# Sheet1.net
KiCad netlist of a schematic drawn in Altium Designer
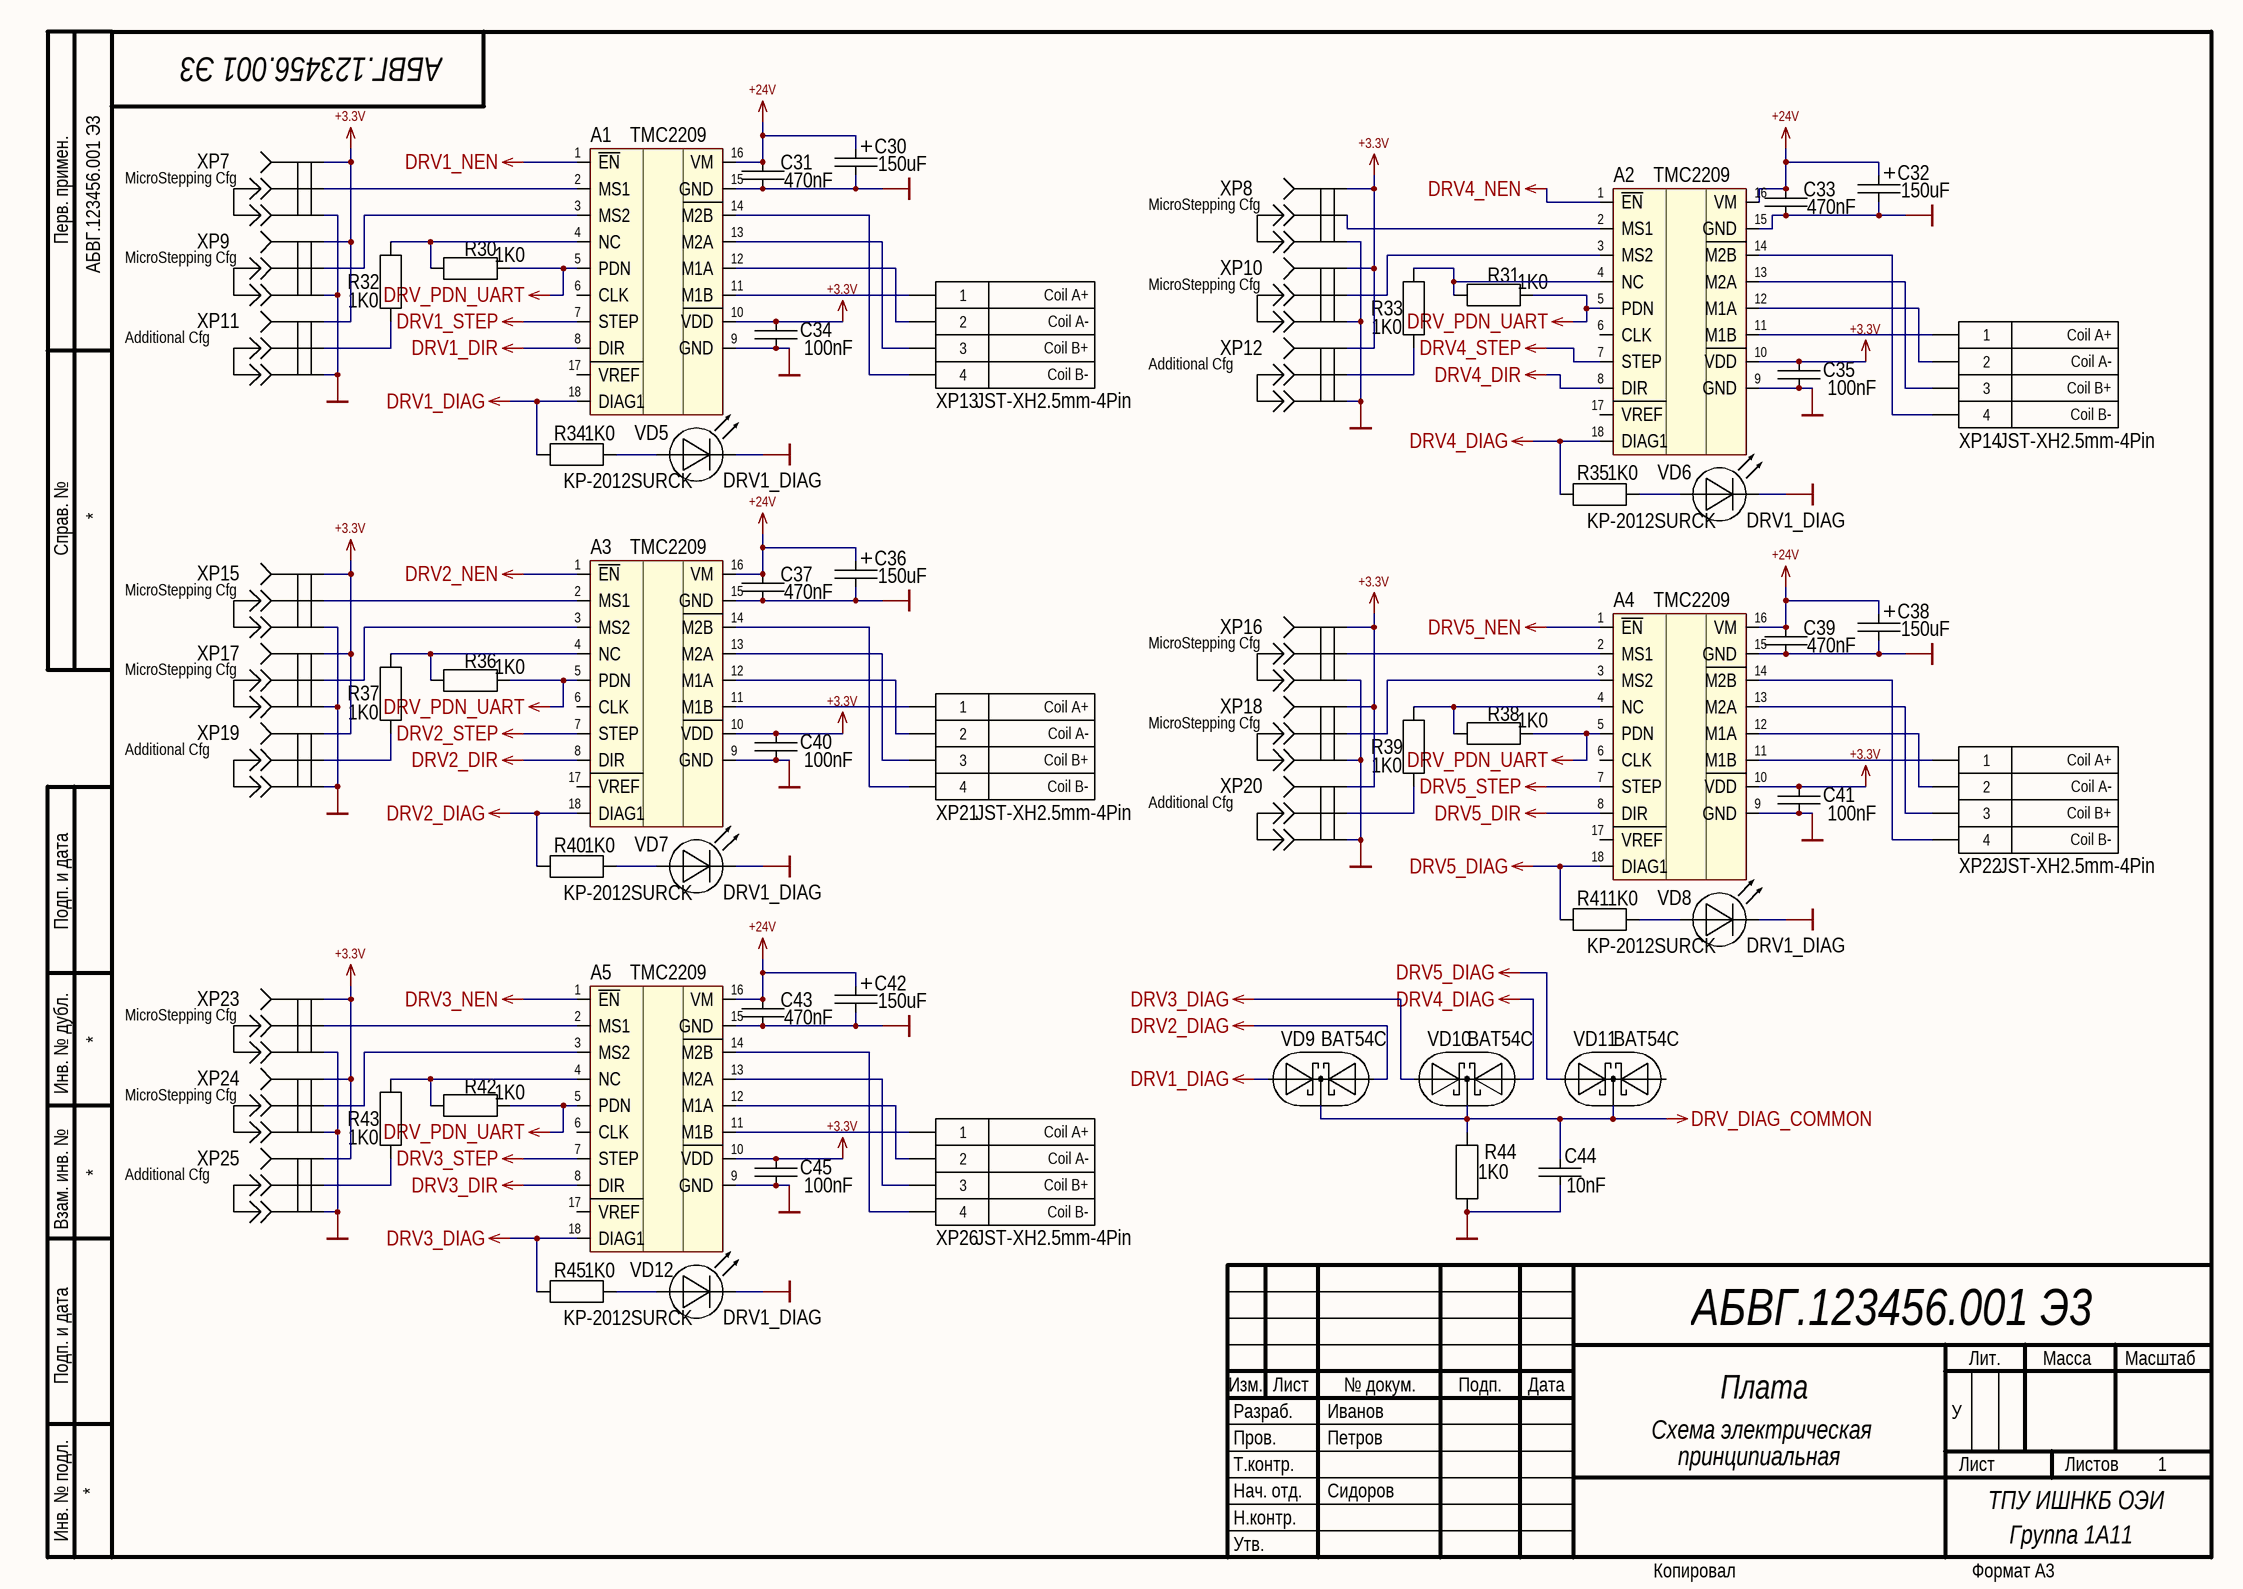
[diagram p0: Sheet1.SchDoc]

(export (version "E")
  (design (tool "Eeschema 10.0.6"))
  (components
    (comp (ref "A1")
      (value "TMC2209")
      (footprint "TMC2209_module")
      (libsource (lib "Digital IC Library") (part "TMC2209_module"))
    )
    (comp (ref "A2")
      (value "TMC2209")
      (footprint "TMC2209_module")
      (libsource (lib "Digital IC Library") (part "TMC2209_module"))
    )
    (comp (ref "A3")
      (value "TMC2209")
      (footprint "TMC2209_module")
      (libsource (lib "Digital IC Library") (part "TMC2209_module"))
    )
    (comp (ref "A4")
      (value "TMC2209")
      (footprint "TMC2209_module")
      (libsource (lib "Digital IC Library") (part "TMC2209_module"))
    )
    (comp (ref "A5")
      (value "TMC2209")
      (footprint "TMC2209_module")
      (libsource (lib "Digital IC Library") (part "TMC2209_module"))
    )
    (comp (ref "C30")
      (value "150uF")
      (footprint "CapAl8X11.5X3.5RA")
      (description "LOW IMPEDANCE ALUMINUM ELECTROLYTIC CAPACITORS CapAl8X11.5X3.5 150uF±20% 35 V 105⁰С")
      (fields (field (name "TOLERANCE") "±20%") (field (name "VOLTAGE") "35 V"))
      (libsource (lib "Passive DataBase") (part "CapacitorPol"))
    )
    (comp (ref "C31")
      (value "470nF")
      (footprint "CAP0805")
      (description "GENERAL PURPOSE CLASS 2 CERAMIC CAPACITORS CAP0805 470nF±10% 50 V X7R")
      (fields (field (name "TOLERANCE") "±10%") (field (name "VOLTAGE") "50 V"))
      (libsource (lib "Passive DataBase") (part "Capacitor"))
    )
    (comp (ref "C32")
      (value "150uF")
      (footprint "CapAl8X11.5X3.5")
      (description "LOW IMPEDANCE ALUMINUM ELECTROLYTIC CAPACITORS CapAl8X11.5X3.5 150uF±20% 35 V 105⁰С")
      (fields (field (name "TOLERANCE") "±20%") (field (name "VOLTAGE") "35 V"))
      (libsource (lib "Passive DataBase") (part "CapacitorPol"))
    )
    (comp (ref "C33")
      (value "470nF")
      (footprint "CAP0805")
      (description "GENERAL PURPOSE CLASS 2 CERAMIC CAPACITORS CAP0805 470nF±10% 50 V X7R")
      (fields (field (name "TOLERANCE") "±10%") (field (name "VOLTAGE") "50 V"))
      (libsource (lib "Passive DataBase") (part "Capacitor"))
    )
    (comp (ref "C34")
      (value "100nF")
      (footprint "CAP0805")
      (description "GENERAL PURPOSE CLASS 2 CERAMIC CAPACITORS CAP0805 100nF±10% 50 V X7R")
      (fields (field (name "TOLERANCE") "±10%") (field (name "VOLTAGE") "50 V"))
      (libsource (lib "Passive DataBase") (part "Capacitor"))
    )
    (comp (ref "C35")
      (value "100nF")
      (footprint "CAP0805")
      (description "GENERAL PURPOSE CLASS 2 CERAMIC CAPACITORS CAP0805 100nF±10% 50 V X7R")
      (fields (field (name "TOLERANCE") "±10%") (field (name "VOLTAGE") "50 V"))
      (libsource (lib "Passive DataBase") (part "Capacitor"))
    )
    (comp (ref "C36")
      (value "150uF")
      (footprint "CapAl8X11.5X3.5RA")
      (description "LOW IMPEDANCE ALUMINUM ELECTROLYTIC CAPACITORS CapAl8X11.5X3.5 150uF±20% 35 V 105⁰С")
      (fields (field (name "TOLERANCE") "±20%") (field (name "VOLTAGE") "35 V"))
      (libsource (lib "Passive DataBase") (part "CapacitorPol"))
    )
    (comp (ref "C37")
      (value "470nF")
      (footprint "CAP0805")
      (description "GENERAL PURPOSE CLASS 2 CERAMIC CAPACITORS CAP0805 470nF±10% 50 V X7R")
      (fields (field (name "TOLERANCE") "±10%") (field (name "VOLTAGE") "50 V"))
      (libsource (lib "Passive DataBase") (part "Capacitor"))
    )
    (comp (ref "C38")
      (value "150uF")
      (footprint "CapAl8X11.5X3.5RA")
      (description "LOW IMPEDANCE ALUMINUM ELECTROLYTIC CAPACITORS CapAl8X11.5X3.5 150uF±20% 35 V 105⁰С")
      (fields (field (name "TOLERANCE") "±20%") (field (name "VOLTAGE") "35 V"))
      (libsource (lib "Passive DataBase") (part "CapacitorPol"))
    )
    (comp (ref "C39")
      (value "470nF")
      (footprint "CAP0805")
      (description "GENERAL PURPOSE CLASS 2 CERAMIC CAPACITORS CAP0805 470nF±10% 50 V X7R")
      (fields (field (name "TOLERANCE") "±10%") (field (name "VOLTAGE") "50 V"))
      (libsource (lib "Passive DataBase") (part "Capacitor"))
    )
    (comp (ref "C40")
      (value "100nF")
      (footprint "CAP0805")
      (description "GENERAL PURPOSE CLASS 2 CERAMIC CAPACITORS CAP0805 100nF±10% 50 V X7R")
      (fields (field (name "TOLERANCE") "±10%") (field (name "VOLTAGE") "50 V"))
      (libsource (lib "Passive DataBase") (part "Capacitor"))
    )
    (comp (ref "C41")
      (value "100nF")
      (footprint "CAP0805")
      (description "GENERAL PURPOSE CLASS 2 CERAMIC CAPACITORS CAP0805 100nF±10% 50 V X7R")
      (fields (field (name "TOLERANCE") "±10%") (field (name "VOLTAGE") "50 V"))
      (libsource (lib "Passive DataBase") (part "Capacitor"))
    )
    (comp (ref "C42")
      (value "150uF")
      (footprint "CapAl8X11.5X3.5RA")
      (description "LOW IMPEDANCE ALUMINUM ELECTROLYTIC CAPACITORS CapAl8X11.5X3.5 150uF±20% 35 V 105⁰С")
      (fields (field (name "TOLERANCE") "±20%") (field (name "VOLTAGE") "35 V"))
      (libsource (lib "Passive DataBase") (part "CapacitorPol"))
    )
    (comp (ref "C43")
      (value "470nF")
      (footprint "CAP0805")
      (description "GENERAL PURPOSE CLASS 2 CERAMIC CAPACITORS CAP0805 470nF±10% 50 V X7R")
      (fields (field (name "TOLERANCE") "±10%") (field (name "VOLTAGE") "50 V"))
      (libsource (lib "Passive DataBase") (part "Capacitor"))
    )
    (comp (ref "C44")
      (value "10nF")
      (footprint "CAP0805")
      (description "GENERAL PURPOSE CLASS 1 CERAMIC CAPACITORS CAP0805 10nF±5% 50 V NP0")
      (fields (field (name "TOLERANCE") "±5%") (field (name "VOLTAGE") "50 V"))
      (libsource (lib "Passive DataBase") (part "Capacitor"))
    )
    (comp (ref "C45")
      (value "100nF")
      (footprint "CAP0805")
      (description "GENERAL PURPOSE CLASS 2 CERAMIC CAPACITORS CAP0805 100nF±10% 50 V X7R")
      (fields (field (name "TOLERANCE") "±10%") (field (name "VOLTAGE") "50 V"))
      (libsource (lib "Passive DataBase") (part "Capacitor"))
    )
    (comp (ref "R30")
      (value "1K0")
      (footprint "RES0805")
      (description "GENERAL PURPOSE CHIP RESISTORS RES0805 1K0±5% 150V 0.125W")
      (fields (field (name "TOLERANCE") "±5%") (field (name "VOLTAGE") "150V"))
      (libsource (lib "Passive DataBase") (part "Resistor"))
    )
    (comp (ref "R31")
      (value "1K0")
      (footprint "RES0805")
      (description "GENERAL PURPOSE CHIP RESISTORS RES0805 1K0±5% 150V 0.125W")
      (fields (field (name "TOLERANCE") "±5%") (field (name "VOLTAGE") "150V"))
      (libsource (lib "Passive DataBase") (part "Resistor"))
    )
    (comp (ref "R32")
      (value "1K0")
      (footprint "RES0805")
      (description "GENERAL PURPOSE CHIP RESISTORS RES0805 1K0±5% 150V 0.125W")
      (fields (field (name "TOLERANCE") "±5%") (field (name "VOLTAGE") "150V"))
      (libsource (lib "Passive DataBase") (part "Resistor"))
    )
    (comp (ref "R33")
      (value "1K0")
      (footprint "RES0805")
      (description "GENERAL PURPOSE CHIP RESISTORS RES0805 1K0±5% 150V 0.125W")
      (fields (field (name "TOLERANCE") "±5%") (field (name "VOLTAGE") "150V"))
      (libsource (lib "Passive DataBase") (part "Resistor"))
    )
    (comp (ref "R34")
      (value "1K0")
      (footprint "RES0805")
      (description "GENERAL PURPOSE CHIP RESISTORS RES0805 1K0±5% 150V 0.125W")
      (fields (field (name "TOLERANCE") "±5%") (field (name "VOLTAGE") "150V"))
      (libsource (lib "Passive DataBase") (part "Resistor"))
    )
    (comp (ref "R35")
      (value "1K0")
      (footprint "RES0805")
      (description "GENERAL PURPOSE CHIP RESISTORS RES0805 1K0±5% 150V 0.125W")
      (fields (field (name "TOLERANCE") "±5%") (field (name "VOLTAGE") "150V"))
      (libsource (lib "Passive DataBase") (part "Resistor"))
    )
    (comp (ref "R36")
      (value "1K0")
      (footprint "RES0805")
      (description "GENERAL PURPOSE CHIP RESISTORS RES0805 1K0±5% 150V 0.125W")
      (fields (field (name "TOLERANCE") "±5%") (field (name "VOLTAGE") "150V"))
      (libsource (lib "Passive DataBase") (part "Resistor"))
    )
    (comp (ref "R37")
      (value "1K0")
      (footprint "RES0805")
      (description "GENERAL PURPOSE CHIP RESISTORS RES0805 1K0±5% 150V 0.125W")
      (fields (field (name "TOLERANCE") "±5%") (field (name "VOLTAGE") "150V"))
      (libsource (lib "Passive DataBase") (part "Resistor"))
    )
    (comp (ref "R38")
      (value "1K0")
      (footprint "RES0805")
      (description "GENERAL PURPOSE CHIP RESISTORS RES0805 1K0±5% 150V 0.125W")
      (fields (field (name "TOLERANCE") "±5%") (field (name "VOLTAGE") "150V"))
      (libsource (lib "Passive DataBase") (part "Resistor"))
    )
    (comp (ref "R39")
      (value "1K0")
      (footprint "RES0805")
      (description "GENERAL PURPOSE CHIP RESISTORS RES0805 1K0±5% 150V 0.125W")
      (fields (field (name "TOLERANCE") "±5%") (field (name "VOLTAGE") "150V"))
      (libsource (lib "Passive DataBase") (part "Resistor"))
    )
    (comp (ref "R40")
      (value "1K0")
      (footprint "RES0805")
      (description "GENERAL PURPOSE CHIP RESISTORS RES0805 1K0±5% 150V 0.125W")
      (fields (field (name "TOLERANCE") "±5%") (field (name "VOLTAGE") "150V"))
      (libsource (lib "Passive DataBase") (part "Resistor"))
    )
    (comp (ref "R41")
      (value "1K0")
      (footprint "RES0805")
      (description "GENERAL PURPOSE CHIP RESISTORS RES0805 1K0±5% 150V 0.125W")
      (fields (field (name "TOLERANCE") "±5%") (field (name "VOLTAGE") "150V"))
      (libsource (lib "Passive DataBase") (part "Resistor"))
    )
    (comp (ref "R42")
      (value "1K0")
      (footprint "RES0805")
      (description "GENERAL PURPOSE CHIP RESISTORS RES0805 1K0±5% 150V 0.125W")
      (fields (field (name "TOLERANCE") "±5%") (field (name "VOLTAGE") "150V"))
      (libsource (lib "Passive DataBase") (part "Resistor"))
    )
    (comp (ref "R43")
      (value "1K0")
      (footprint "RES0805")
      (description "GENERAL PURPOSE CHIP RESISTORS RES0805 1K0±5% 150V 0.125W")
      (fields (field (name "TOLERANCE") "±5%") (field (name "VOLTAGE") "150V"))
      (libsource (lib "Passive DataBase") (part "Resistor"))
    )
    (comp (ref "R44")
      (value "1K0")
      (footprint "RES0805")
      (description "GENERAL PURPOSE CHIP RESISTORS RES0805 1K0±5% 150V 0.125W")
      (fields (field (name "TOLERANCE") "±5%") (field (name "VOLTAGE") "150V"))
      (libsource (lib "Passive DataBase") (part "Resistor"))
    )
    (comp (ref "R45")
      (value "1K0")
      (footprint "RES0805")
      (description "GENERAL PURPOSE CHIP RESISTORS RES0805 1K0±5% 150V 0.125W")
      (fields (field (name "TOLERANCE") "±5%") (field (name "VOLTAGE") "150V"))
      (libsource (lib "Passive DataBase") (part "Resistor"))
    )
    (comp (ref "VD5")
      (value "KP-2012SURCK (2.0V, 25mA, LED0805 RED)")
      (footprint "LED0805 RED")
      (description "LED SMD KP-2012SURCK (2.0V, 25mA, LED0805 RED)")
      (fields
        (field (name "MODEL") "KP-2012SURCK")
        (field (name "VOLTAGE") "2.0V")
        (field (name "PARTNUMBER") "KP-2012SURCK")
      )
      (libsource (lib "Discrete Semiconductors DataBase") (part "LED Single"))
    )
    (comp (ref "VD6")
      (value "KP-2012SURCK (2.0V, 25mA, LED0805 RED)")
      (footprint "LED0805 RED")
      (description "LED SMD KP-2012SURCK (2.0V, 25mA, LED0805 RED)")
      (fields
        (field (name "MODEL") "KP-2012SURCK")
        (field (name "VOLTAGE") "2.0V")
        (field (name "PARTNUMBER") "KP-2012SURCK")
      )
      (libsource (lib "Discrete Semiconductors DataBase") (part "LED Single"))
    )
    (comp (ref "VD7")
      (value "KP-2012SURCK (2.0V, 25mA, LED0805 RED)")
      (footprint "LED0805 RED")
      (description "LED SMD KP-2012SURCK (2.0V, 25mA, LED0805 RED)")
      (fields
        (field (name "MODEL") "KP-2012SURCK")
        (field (name "VOLTAGE") "2.0V")
        (field (name "PARTNUMBER") "KP-2012SURCK")
      )
      (libsource (lib "Discrete Semiconductors DataBase") (part "LED Single"))
    )
    (comp (ref "VD8")
      (value "KP-2012SURCK (2.0V, 25mA, LED0805 RED)")
      (footprint "LED0805 RED")
      (description "LED SMD KP-2012SURCK (2.0V, 25mA, LED0805 RED)")
      (fields
        (field (name "MODEL") "KP-2012SURCK")
        (field (name "VOLTAGE") "2.0V")
        (field (name "PARTNUMBER") "KP-2012SURCK")
      )
      (libsource (lib "Discrete Semiconductors DataBase") (part "LED Single"))
    )
    (comp (ref "VD9")
      (value "BAT54C (30 V, 200 mA, SOT23-3 DIODE (A1A2C))")
      (footprint "SOT23-3 DIODE (A1A2C)")
      (description "DIODE BAT54C (30 V, 200 mA, SOT23-3 DIODE (A1A2C), NXP)")
      (fields
        (field (name "MODEL") "BAT54C")
        (field (name "VOLTAGE") "30 V")
        (field (name "PARTNUMBER") "BAT54C,215")
      )
      (libsource (lib "Discrete Semiconductors DataBase") (part "Common Cathode Schottky Diodes"))
    )
    (comp (ref "VD10")
      (value "BAT54C (30 V, 200 mA, SOT23-3 DIODE (A1A2C))")
      (footprint "SOT23-3 DIODE (A1A2C)")
      (description "DIODE BAT54C (30 V, 200 mA, SOT23-3 DIODE (A1A2C), NXP)")
      (fields
        (field (name "MODEL") "BAT54C")
        (field (name "VOLTAGE") "30 V")
        (field (name "PARTNUMBER") "BAT54C,215")
      )
      (libsource (lib "Discrete Semiconductors DataBase") (part "Common Cathode Schottky Diodes"))
    )
    (comp (ref "VD11")
      (value "BAT54C (30 V, 200 mA, SOT23-3 DIODE (A1A2C))")
      (footprint "SOT23-3 DIODE (A1A2C)")
      (description "DIODE BAT54C (30 V, 200 mA, SOT23-3 DIODE (A1A2C), NXP)")
      (fields
        (field (name "MODEL") "BAT54C")
        (field (name "VOLTAGE") "30 V")
        (field (name "PARTNUMBER") "BAT54C,215")
      )
      (libsource (lib "Discrete Semiconductors DataBase") (part "Common Cathode Schottky Diodes"))
    )
    (comp (ref "VD12")
      (value "KP-2012SURCK (2.0V, 25mA, LED0805 RED)")
      (footprint "LED0805 RED")
      (description "LED SMD KP-2012SURCK (2.0V, 25mA, LED0805 RED)")
      (fields
        (field (name "MODEL") "KP-2012SURCK")
        (field (name "VOLTAGE") "2.0V")
        (field (name "PARTNUMBER") "KP-2012SURCK")
      )
      (libsource (lib "Discrete Semiconductors DataBase") (part "LED Single"))
    )
    (comp (ref "XP7")
      (value "PLS-3 1х3 Jumper")
      (footprint "PLS-1-3")
      (description "PLS-3, Вилка штыревая 2.54мм 1х3pin прямая (тип D1)")
      (libsource (lib "Connectors Library") (part "PLS-3 1х3 Jumper"))
    )
    (comp (ref "XP8")
      (value "PLS-3 1х3 Jumper")
      (footprint "PLS-1-3")
      (description "PLS-3, Вилка штыревая 2.54мм 1х3pin прямая (тип D1)")
      (libsource (lib "Connectors Library") (part "PLS-3 1х3 Jumper"))
    )
    (comp (ref "XP9")
      (value "PLS-3 1х3 Jumper")
      (footprint "PLS-1-3")
      (description "PLS-3, Вилка штыревая 2.54мм 1х3pin прямая (тип D1)")
      (libsource (lib "Connectors Library") (part "PLS-3 1х3 Jumper"))
    )
    (comp (ref "XP10")
      (value "PLS-3 1х3 Jumper")
      (footprint "PLS-1-3")
      (description "PLS-3, Вилка штыревая 2.54мм 1х3pin прямая (тип D1)")
      (libsource (lib "Connectors Library") (part "PLS-3 1х3 Jumper"))
    )
    (comp (ref "XP11")
      (value "PLS-3 1х3 Jumper")
      (footprint "PLS-1-3")
      (description "PLS-3, Вилка штыревая 2.54мм 1х3pin прямая (тип D1)")
      (libsource (lib "Connectors Library") (part "PLS-3 1х3 Jumper"))
    )
    (comp (ref "XP12")
      (value "PLS-3 1х3 Jumper")
      (footprint "PLS-1-3")
      (description "PLS-3, Вилка штыревая 2.54мм 1х3pin прямая (тип D1)")
      (libsource (lib "Connectors Library") (part "PLS-3 1х3 Jumper"))
    )
    (comp (ref "XP13")
      (value "JST-XH2.5mm-4Pin")
      (footprint "JST-XH2.5-4")
      (description "2.5 mm pitch/Wire-to-Board connectors. Male Curved Needle Plug")
      (fields
        (field (name "PIN 4 NAME") "Coil B-")
        (field (name "PIN 3 NAME") "Coil B+")
        (field (name "PIN 2 NAME") "Coil A-")
        (field (name "PIN 1 NAME") "Coil A+")
      )
      (libsource (lib "Connectors Library") (part "JST-XH2.5mm-4Pin"))
    )
    (comp (ref "XP14")
      (value "JST-XH2.5mm-4Pin")
      (footprint "JST-XH2.5-4")
      (description "2.5 mm pitch/Wire-to-Board connectors. Male Curved Needle Plug")
      (fields
        (field (name "PIN 4 NAME") "Coil B-")
        (field (name "PIN 3 NAME") "Coil B+")
        (field (name "PIN 2 NAME") "Coil A-")
        (field (name "PIN 1 NAME") "Coil A+")
      )
      (libsource (lib "Connectors Library") (part "JST-XH2.5mm-4Pin"))
    )
    (comp (ref "XP15")
      (value "PLS-3 1х3 Jumper")
      (footprint "PLS-1-3")
      (description "PLS-3, Вилка штыревая 2.54мм 1х3pin прямая (тип D1)")
      (libsource (lib "Connectors Library") (part "PLS-3 1х3 Jumper"))
    )
    (comp (ref "XP16")
      (value "PLS-3 1х3 Jumper")
      (footprint "PLS-1-3")
      (description "PLS-3, Вилка штыревая 2.54мм 1х3pin прямая (тип D1)")
      (libsource (lib "Connectors Library") (part "PLS-3 1х3 Jumper"))
    )
    (comp (ref "XP17")
      (value "PLS-3 1х3 Jumper")
      (footprint "PLS-1-3")
      (description "PLS-3, Вилка штыревая 2.54мм 1х3pin прямая (тип D1)")
      (libsource (lib "Connectors Library") (part "PLS-3 1х3 Jumper"))
    )
    (comp (ref "XP18")
      (value "PLS-3 1х3 Jumper")
      (footprint "PLS-1-3")
      (description "PLS-3, Вилка штыревая 2.54мм 1х3pin прямая (тип D1)")
      (libsource (lib "Connectors Library") (part "PLS-3 1х3 Jumper"))
    )
    (comp (ref "XP19")
      (value "PLS-3 1х3 Jumper")
      (footprint "PLS-1-3")
      (description "PLS-3, Вилка штыревая 2.54мм 1х3pin прямая (тип D1)")
      (libsource (lib "Connectors Library") (part "PLS-3 1х3 Jumper"))
    )
    (comp (ref "XP20")
      (value "PLS-3 1х3 Jumper")
      (footprint "PLS-1-3")
      (description "PLS-3, Вилка штыревая 2.54мм 1х3pin прямая (тип D1)")
      (libsource (lib "Connectors Library") (part "PLS-3 1х3 Jumper"))
    )
    (comp (ref "XP21")
      (value "JST-XH2.5mm-4Pin")
      (footprint "JST-XH2.5-4")
      (description "2.5 mm pitch/Wire-to-Board connectors. Male Curved Needle Plug")
      (fields
        (field (name "PIN 4 NAME") "Coil B-")
        (field (name "PIN 3 NAME") "Coil B+")
        (field (name "PIN 2 NAME") "Coil A-")
        (field (name "PIN 1 NAME") "Coil A+")
      )
      (libsource (lib "Connectors Library") (part "JST-XH2.5mm-4Pin"))
    )
    (comp (ref "XP22")
      (value "JST-XH2.5mm-4Pin")
      (footprint "JST-XH2.5-4")
      (description "2.5 mm pitch/Wire-to-Board connectors. Male Curved Needle Plug")
      (fields
        (field (name "PIN 4 NAME") "Coil B-")
        (field (name "PIN 3 NAME") "Coil B+")
        (field (name "PIN 2 NAME") "Coil A-")
        (field (name "PIN 1 NAME") "Coil A+")
      )
      (libsource (lib "Connectors Library") (part "JST-XH2.5mm-4Pin"))
    )
    (comp (ref "XP23")
      (value "PLS-3 1х3 Jumper")
      (footprint "PLS-1-3")
      (description "PLS-3, Вилка штыревая 2.54мм 1х3pin прямая (тип D1)")
      (libsource (lib "Connectors Library") (part "PLS-3 1х3 Jumper"))
    )
    (comp (ref "XP24")
      (value "PLS-3 1х3 Jumper")
      (footprint "PLS-1-3")
      (description "PLS-3, Вилка штыревая 2.54мм 1х3pin прямая (тип D1)")
      (libsource (lib "Connectors Library") (part "PLS-3 1х3 Jumper"))
    )
    (comp (ref "XP25")
      (value "PLS-3 1х3 Jumper")
      (footprint "PLS-1-3")
      (description "PLS-3, Вилка штыревая 2.54мм 1х3pin прямая (тип D1)")
      (libsource (lib "Connectors Library") (part "PLS-3 1х3 Jumper"))
    )
    (comp (ref "XP26")
      (value "JST-XH2.5mm-4Pin")
      (footprint "JST-XH2.5-4")
      (description "2.5 mm pitch/Wire-to-Board connectors. Male Curved Needle Plug")
      (fields
        (field (name "PIN 4 NAME") "Coil B-")
        (field (name "PIN 3 NAME") "Coil B+")
        (field (name "PIN 2 NAME") "Coil A-")
        (field (name "PIN 1 NAME") "Coil A+")
      )
      (libsource (lib "Connectors Library") (part "JST-XH2.5mm-4Pin"))
    )
  )
  (nets
    (net (code "1") (name "+3.3V") (class "Default")
      (node (ref "A1") (pin "10") (pinfunction "VDD_10") (pintype "passive"))
      (node (ref "A2") (pin "10") (pinfunction "VDD_10") (pintype "passive"))
      (node (ref "A3") (pin "10") (pinfunction "VDD_10") (pintype "passive"))
      (node (ref "A4") (pin "10") (pinfunction "VDD_10") (pintype "passive"))
      (node (ref "A5") (pin "10") (pinfunction "VDD_10") (pintype "passive"))
      (node (ref "C34") (pin "1") (pinfunction "1_1") (pintype "passive"))
      (node (ref "C35") (pin "1") (pinfunction "1_1") (pintype "passive"))
      (node (ref "C40") (pin "1") (pinfunction "1_1") (pintype "passive"))
      (node (ref "C41") (pin "1") (pinfunction "1_1") (pintype "passive"))
      (node (ref "C45") (pin "1") (pinfunction "1_1") (pintype "passive"))
      (node (ref "XP10") (pin "1") (pinfunction "1_1") (pintype "passive"))
      (node (ref "XP11") (pin "1") (pinfunction "1_1") (pintype "passive"))
      (node (ref "XP12") (pin "1") (pinfunction "1_1") (pintype "passive"))
      (node (ref "XP15") (pin "1") (pinfunction "1_1") (pintype "passive"))
      (node (ref "XP16") (pin "1") (pinfunction "1_1") (pintype "passive"))
      (node (ref "XP17") (pin "1") (pinfunction "1_1") (pintype "passive"))
      (node (ref "XP18") (pin "1") (pinfunction "1_1") (pintype "passive"))
      (node (ref "XP19") (pin "1") (pinfunction "1_1") (pintype "passive"))
      (node (ref "XP20") (pin "1") (pinfunction "1_1") (pintype "passive"))
      (node (ref "XP23") (pin "1") (pinfunction "1_1") (pintype "passive"))
      (node (ref "XP24") (pin "1") (pinfunction "1_1") (pintype "passive"))
      (node (ref "XP25") (pin "1") (pinfunction "1_1") (pintype "passive"))
      (node (ref "XP7") (pin "1") (pinfunction "1_1") (pintype "passive"))
      (node (ref "XP8") (pin "1") (pinfunction "1_1") (pintype "passive"))
      (node (ref "XP9") (pin "1") (pinfunction "1_1") (pintype "passive"))
    )
    (net (code "2") (name "+24V") (class "Default")
      (node (ref "A1") (pin "16") (pinfunction "VM_16") (pintype "passive"))
      (node (ref "A2") (pin "16") (pinfunction "VM_16") (pintype "passive"))
      (node (ref "A3") (pin "16") (pinfunction "VM_16") (pintype "passive"))
      (node (ref "A4") (pin "16") (pinfunction "VM_16") (pintype "passive"))
      (node (ref "A5") (pin "16") (pinfunction "VM_16") (pintype "passive"))
      (node (ref "C30") (pin "1") (pinfunction "1_1") (pintype "passive"))
      (node (ref "C31") (pin "2") (pinfunction "2_2") (pintype "passive"))
      (node (ref "C32") (pin "1") (pinfunction "1_1") (pintype "passive"))
      (node (ref "C33") (pin "2") (pinfunction "2_2") (pintype "passive"))
      (node (ref "C36") (pin "1") (pinfunction "1_1") (pintype "passive"))
      (node (ref "C37") (pin "2") (pinfunction "2_2") (pintype "passive"))
      (node (ref "C38") (pin "1") (pinfunction "1_1") (pintype "passive"))
      (node (ref "C39") (pin "2") (pinfunction "2_2") (pintype "passive"))
      (node (ref "C42") (pin "1") (pinfunction "1_1") (pintype "passive"))
      (node (ref "C43") (pin "2") (pinfunction "2_2") (pintype "passive"))
    )
    (net (code "3") (name "DRV1_DIAG") (class "Default")
      (node (ref "A1") (pin "18") (pinfunction "DIAG1_18") (pintype "passive"))
      (node (ref "R34") (pin "1") (pinfunction "1_1") (pintype "passive"))
      (node (ref "VD9") (pin "Anode1") (pinfunction "First_Diod_Anode_Anode1") (pintype "passive"))
    )
    (net (code "4") (name "DRV1_DIR") (class "Default")
      (node (ref "A1") (pin "8") (pinfunction "DIR_8") (pintype "passive"))
    )
    (net (code "5") (name "DRV1_NEN") (class "Default")
      (node (ref "A1") (pin "1") (pinfunction "~{EN}_1") (pintype "passive"))
    )
    (net (code "6") (name "DRV1_STEP") (class "Default")
      (node (ref "A1") (pin "7") (pinfunction "STEP_7") (pintype "passive"))
    )
    (net (code "7") (name "DRV2_DIAG") (class "Default")
      (node (ref "A3") (pin "18") (pinfunction "DIAG1_18") (pintype "passive"))
      (node (ref "R40") (pin "1") (pinfunction "1_1") (pintype "passive"))
      (node (ref "VD9") (pin "Anode2") (pinfunction "Second_Diod_Anode_Anode2") (pintype "passive"))
    )
    (net (code "8") (name "DRV2_DIR") (class "Default")
      (node (ref "A3") (pin "8") (pinfunction "DIR_8") (pintype "passive"))
    )
    (net (code "9") (name "DRV2_NEN") (class "Default")
      (node (ref "A3") (pin "1") (pinfunction "~{EN}_1") (pintype "passive"))
    )
    (net (code "10") (name "DRV2_STEP") (class "Default")
      (node (ref "A3") (pin "7") (pinfunction "STEP_7") (pintype "passive"))
    )
    (net (code "11") (name "DRV3_DIAG") (class "Default")
      (node (ref "A5") (pin "18") (pinfunction "DIAG1_18") (pintype "passive"))
      (node (ref "R45") (pin "1") (pinfunction "1_1") (pintype "passive"))
      (node (ref "VD10") (pin "Anode1") (pinfunction "First_Diod_Anode_Anode1") (pintype "passive"))
    )
    (net (code "12") (name "DRV3_DIR") (class "Default")
      (node (ref "A5") (pin "8") (pinfunction "DIR_8") (pintype "passive"))
    )
    (net (code "13") (name "DRV3_NEN") (class "Default")
      (node (ref "A5") (pin "1") (pinfunction "~{EN}_1") (pintype "passive"))
    )
    (net (code "14") (name "DRV3_STEP") (class "Default")
      (node (ref "A5") (pin "7") (pinfunction "STEP_7") (pintype "passive"))
    )
    (net (code "15") (name "DRV4_DIAG") (class "Default")
      (node (ref "A2") (pin "18") (pinfunction "DIAG1_18") (pintype "passive"))
      (node (ref "R35") (pin "1") (pinfunction "1_1") (pintype "passive"))
      (node (ref "VD10") (pin "Anode2") (pinfunction "Second_Diod_Anode_Anode2") (pintype "passive"))
    )
    (net (code "16") (name "DRV4_DIR") (class "Default")
      (node (ref "A2") (pin "8") (pinfunction "DIR_8") (pintype "passive"))
    )
    (net (code "17") (name "DRV4_NEN") (class "Default")
      (node (ref "A2") (pin "1") (pinfunction "~{EN}_1") (pintype "passive"))
    )
    (net (code "18") (name "DRV4_STEP") (class "Default")
      (node (ref "A2") (pin "7") (pinfunction "STEP_7") (pintype "passive"))
    )
    (net (code "19") (name "DRV5_DIAG") (class "Default")
      (node (ref "A4") (pin "18") (pinfunction "DIAG1_18") (pintype "passive"))
      (node (ref "R41") (pin "1") (pinfunction "1_1") (pintype "passive"))
      (node (ref "VD11") (pin "Anode1") (pinfunction "First_Diod_Anode_Anode1") (pintype "passive"))
    )
    (net (code "20") (name "DRV5_DIR") (class "Default")
      (node (ref "A4") (pin "8") (pinfunction "DIR_8") (pintype "passive"))
    )
    (net (code "21") (name "DRV5_NEN") (class "Default")
      (node (ref "A4") (pin "1") (pinfunction "~{EN}_1") (pintype "passive"))
    )
    (net (code "22") (name "DRV5_STEP") (class "Default")
      (node (ref "A4") (pin "7") (pinfunction "STEP_7") (pintype "passive"))
    )
    (net (code "23") (name "DRV_DIAG_COMMON") (class "Default")
      (node (ref "C44") (pin "2") (pinfunction "2_2") (pintype "passive"))
      (node (ref "R44") (pin "1") (pinfunction "1_1") (pintype "passive"))
      (node (ref "VD10") (pin "Common") (pinfunction "Common_Cathodes_Common") (pintype "passive"))
      (node (ref "VD11") (pin "Common") (pinfunction "Common_Cathodes_Common") (pintype "passive"))
      (node (ref "VD9") (pin "Common") (pinfunction "Common_Cathodes_Common") (pintype "passive"))
    )
    (net (code "24") (name "DRV_PDN_UART") (class "Default")
      (node (ref "A1") (pin "5") (pinfunction "PDN_5") (pintype "passive"))
      (node (ref "A2") (pin "5") (pinfunction "PDN_5") (pintype "passive"))
      (node (ref "A3") (pin "5") (pinfunction "PDN_5") (pintype "passive"))
      (node (ref "A4") (pin "5") (pinfunction "PDN_5") (pintype "passive"))
      (node (ref "A5") (pin "5") (pinfunction "PDN_5") (pintype "passive"))
      (node (ref "R30") (pin "2") (pinfunction "2_2") (pintype "passive"))
      (node (ref "R31") (pin "2") (pinfunction "2_2") (pintype "passive"))
      (node (ref "R36") (pin "2") (pinfunction "2_2") (pintype "passive"))
      (node (ref "R38") (pin "2") (pinfunction "2_2") (pintype "passive"))
      (node (ref "R42") (pin "2") (pinfunction "2_2") (pintype "passive"))
    )
    (net (code "25") (name "GND") (class "Default")
      (node (ref "A1") (pin "15") (pinfunction "GND_15") (pintype "passive"))
      (node (ref "A1") (pin "9") (pinfunction "GND_9") (pintype "passive"))
      (node (ref "A2") (pin "15") (pinfunction "GND_15") (pintype "passive"))
      (node (ref "A2") (pin "9") (pinfunction "GND_9") (pintype "passive"))
      (node (ref "A3") (pin "15") (pinfunction "GND_15") (pintype "passive"))
      (node (ref "A3") (pin "9") (pinfunction "GND_9") (pintype "passive"))
      (node (ref "A4") (pin "15") (pinfunction "GND_15") (pintype "passive"))
      (node (ref "A4") (pin "9") (pinfunction "GND_9") (pintype "passive"))
      (node (ref "A5") (pin "15") (pinfunction "GND_15") (pintype "passive"))
      (node (ref "A5") (pin "9") (pinfunction "GND_9") (pintype "passive"))
      (node (ref "C30") (pin "2") (pinfunction "2_2") (pintype "passive"))
      (node (ref "C31") (pin "1") (pinfunction "1_1") (pintype "passive"))
      (node (ref "C32") (pin "2") (pinfunction "2_2") (pintype "passive"))
      (node (ref "C33") (pin "1") (pinfunction "1_1") (pintype "passive"))
      (node (ref "C34") (pin "2") (pinfunction "2_2") (pintype "passive"))
      (node (ref "C35") (pin "2") (pinfunction "2_2") (pintype "passive"))
      (node (ref "C36") (pin "2") (pinfunction "2_2") (pintype "passive"))
      (node (ref "C37") (pin "1") (pinfunction "1_1") (pintype "passive"))
      (node (ref "C38") (pin "2") (pinfunction "2_2") (pintype "passive"))
      (node (ref "C39") (pin "1") (pinfunction "1_1") (pintype "passive"))
      (node (ref "C40") (pin "2") (pinfunction "2_2") (pintype "passive"))
      (node (ref "C41") (pin "2") (pinfunction "2_2") (pintype "passive"))
      (node (ref "C42") (pin "2") (pinfunction "2_2") (pintype "passive"))
      (node (ref "C43") (pin "1") (pinfunction "1_1") (pintype "passive"))
      (node (ref "C44") (pin "1") (pinfunction "1_1") (pintype "passive"))
      (node (ref "C45") (pin "2") (pinfunction "2_2") (pintype "passive"))
      (node (ref "R44") (pin "2") (pinfunction "2_2") (pintype "passive"))
      (node (ref "VD12") (pin "Cathode") (pinfunction "Cathode_Cathode") (pintype "passive"))
      (node (ref "VD5") (pin "Cathode") (pinfunction "Cathode_Cathode") (pintype "passive"))
      (node (ref "VD6") (pin "Cathode") (pinfunction "Cathode_Cathode") (pintype "passive"))
      (node (ref "VD7") (pin "Cathode") (pinfunction "Cathode_Cathode") (pintype "passive"))
      (node (ref "VD8") (pin "Cathode") (pinfunction "Cathode_Cathode") (pintype "passive"))
      (node (ref "XP10") (pin "3") (pinfunction "3_3") (pintype "passive"))
      (node (ref "XP11") (pin "3") (pinfunction "3_3") (pintype "passive"))
      (node (ref "XP12") (pin "3") (pinfunction "3_3") (pintype "passive"))
      (node (ref "XP15") (pin "3") (pinfunction "3_3") (pintype "passive"))
      (node (ref "XP16") (pin "3") (pinfunction "3_3") (pintype "passive"))
      (node (ref "XP17") (pin "3") (pinfunction "3_3") (pintype "passive"))
      (node (ref "XP18") (pin "3") (pinfunction "3_3") (pintype "passive"))
      (node (ref "XP19") (pin "3") (pinfunction "3_3") (pintype "passive"))
      (node (ref "XP20") (pin "3") (pinfunction "3_3") (pintype "passive"))
      (node (ref "XP23") (pin "3") (pinfunction "3_3") (pintype "passive"))
      (node (ref "XP24") (pin "3") (pinfunction "3_3") (pintype "passive"))
      (node (ref "XP25") (pin "3") (pinfunction "3_3") (pintype "passive"))
      (node (ref "XP7") (pin "3") (pinfunction "3_3") (pintype "passive"))
      (node (ref "XP8") (pin "3") (pinfunction "3_3") (pintype "passive"))
      (node (ref "XP9") (pin "3") (pinfunction "3_3") (pintype "passive"))
    )
    (net (code "26") (name "Net-(A1-M1A)") (class "Default")
      (node (ref "A1") (pin "12") (pinfunction "M1A_12") (pintype "passive"))
      (node (ref "XP13") (pin "2") (pinfunction "2_2") (pintype "passive"))
    )
    (net (code "27") (name "Net-(A1-M1B)") (class "Default")
      (node (ref "A1") (pin "11") (pinfunction "M1B_11") (pintype "passive"))
      (node (ref "XP13") (pin "1") (pinfunction "1_1") (pintype "passive"))
    )
    (net (code "28") (name "Net-(A1-M2A)") (class "Default")
      (node (ref "A1") (pin "13") (pinfunction "M2A_13") (pintype "passive"))
      (node (ref "XP13") (pin "3") (pinfunction "3_3") (pintype "passive"))
    )
    (net (code "29") (name "Net-(A1-M2B)") (class "Default")
      (node (ref "A1") (pin "14") (pinfunction "M2B_14") (pintype "passive"))
      (node (ref "XP13") (pin "4") (pinfunction "4_4") (pintype "passive"))
    )
    (net (code "30") (name "Net-(A1-MS1)") (class "Default")
      (node (ref "A1") (pin "2") (pinfunction "MS1_2") (pintype "passive"))
      (node (ref "XP7") (pin "2") (pinfunction "2_2") (pintype "passive"))
    )
    (net (code "31") (name "Net-(A1-MS2)") (class "Default")
      (node (ref "A1") (pin "3") (pinfunction "MS2_3") (pintype "passive"))
      (node (ref "XP9") (pin "2") (pinfunction "2_2") (pintype "passive"))
    )
    (net (code "32") (name "Net-(A1-NC)") (class "Default")
      (node (ref "A1") (pin "4") (pinfunction "NC_4") (pintype "passive"))
      (node (ref "R30") (pin "1") (pinfunction "1_1") (pintype "passive"))
      (node (ref "R32") (pin "2") (pinfunction "2_2") (pintype "passive"))
    )
    (net (code "33") (name "Net-(A2-M1A)") (class "Default")
      (node (ref "A2") (pin "12") (pinfunction "M1A_12") (pintype "passive"))
      (node (ref "XP14") (pin "2") (pinfunction "2_2") (pintype "passive"))
    )
    (net (code "34") (name "Net-(A2-M1B)") (class "Default")
      (node (ref "A2") (pin "11") (pinfunction "M1B_11") (pintype "passive"))
      (node (ref "XP14") (pin "1") (pinfunction "1_1") (pintype "passive"))
    )
    (net (code "35") (name "Net-(A2-M2A)") (class "Default")
      (node (ref "A2") (pin "13") (pinfunction "M2A_13") (pintype "passive"))
      (node (ref "XP14") (pin "3") (pinfunction "3_3") (pintype "passive"))
    )
    (net (code "36") (name "Net-(A2-M2B)") (class "Default")
      (node (ref "A2") (pin "14") (pinfunction "M2B_14") (pintype "passive"))
      (node (ref "XP14") (pin "4") (pinfunction "4_4") (pintype "passive"))
    )
    (net (code "37") (name "Net-(A2-MS1)") (class "Default")
      (node (ref "A2") (pin "2") (pinfunction "MS1_2") (pintype "passive"))
      (node (ref "XP8") (pin "2") (pinfunction "2_2") (pintype "passive"))
    )
    (net (code "38") (name "Net-(A2-MS2)") (class "Default")
      (node (ref "A2") (pin "3") (pinfunction "MS2_3") (pintype "passive"))
      (node (ref "XP10") (pin "2") (pinfunction "2_2") (pintype "passive"))
    )
    (net (code "39") (name "Net-(A2-NC)") (class "Default")
      (node (ref "A2") (pin "4") (pinfunction "NC_4") (pintype "passive"))
      (node (ref "R31") (pin "1") (pinfunction "1_1") (pintype "passive"))
      (node (ref "R33") (pin "2") (pinfunction "2_2") (pintype "passive"))
    )
    (net (code "40") (name "Net-(A3-M1A)") (class "Default")
      (node (ref "A3") (pin "12") (pinfunction "M1A_12") (pintype "passive"))
      (node (ref "XP21") (pin "2") (pinfunction "2_2") (pintype "passive"))
    )
    (net (code "41") (name "Net-(A3-M1B)") (class "Default")
      (node (ref "A3") (pin "11") (pinfunction "M1B_11") (pintype "passive"))
      (node (ref "XP21") (pin "1") (pinfunction "1_1") (pintype "passive"))
    )
    (net (code "42") (name "Net-(A3-M2A)") (class "Default")
      (node (ref "A3") (pin "13") (pinfunction "M2A_13") (pintype "passive"))
      (node (ref "XP21") (pin "3") (pinfunction "3_3") (pintype "passive"))
    )
    (net (code "43") (name "Net-(A3-M2B)") (class "Default")
      (node (ref "A3") (pin "14") (pinfunction "M2B_14") (pintype "passive"))
      (node (ref "XP21") (pin "4") (pinfunction "4_4") (pintype "passive"))
    )
    (net (code "44") (name "Net-(A3-MS1)") (class "Default")
      (node (ref "A3") (pin "2") (pinfunction "MS1_2") (pintype "passive"))
      (node (ref "XP15") (pin "2") (pinfunction "2_2") (pintype "passive"))
    )
    (net (code "45") (name "Net-(A3-MS2)") (class "Default")
      (node (ref "A3") (pin "3") (pinfunction "MS2_3") (pintype "passive"))
      (node (ref "XP17") (pin "2") (pinfunction "2_2") (pintype "passive"))
    )
    (net (code "46") (name "Net-(A3-NC)") (class "Default")
      (node (ref "A3") (pin "4") (pinfunction "NC_4") (pintype "passive"))
      (node (ref "R36") (pin "1") (pinfunction "1_1") (pintype "passive"))
      (node (ref "R37") (pin "2") (pinfunction "2_2") (pintype "passive"))
    )
    (net (code "47") (name "Net-(A4-M1A)") (class "Default")
      (node (ref "A4") (pin "12") (pinfunction "M1A_12") (pintype "passive"))
      (node (ref "XP22") (pin "2") (pinfunction "2_2") (pintype "passive"))
    )
    (net (code "48") (name "Net-(A4-M1B)") (class "Default")
      (node (ref "A4") (pin "11") (pinfunction "M1B_11") (pintype "passive"))
      (node (ref "XP22") (pin "1") (pinfunction "1_1") (pintype "passive"))
    )
    (net (code "49") (name "Net-(A4-M2A)") (class "Default")
      (node (ref "A4") (pin "13") (pinfunction "M2A_13") (pintype "passive"))
      (node (ref "XP22") (pin "3") (pinfunction "3_3") (pintype "passive"))
    )
    (net (code "50") (name "Net-(A4-M2B)") (class "Default")
      (node (ref "A4") (pin "14") (pinfunction "M2B_14") (pintype "passive"))
      (node (ref "XP22") (pin "4") (pinfunction "4_4") (pintype "passive"))
    )
    (net (code "51") (name "Net-(A4-MS1)") (class "Default")
      (node (ref "A4") (pin "2") (pinfunction "MS1_2") (pintype "passive"))
      (node (ref "XP16") (pin "2") (pinfunction "2_2") (pintype "passive"))
    )
    (net (code "52") (name "Net-(A4-MS2)") (class "Default")
      (node (ref "A4") (pin "3") (pinfunction "MS2_3") (pintype "passive"))
      (node (ref "XP18") (pin "2") (pinfunction "2_2") (pintype "passive"))
    )
    (net (code "53") (name "Net-(A4-NC)") (class "Default")
      (node (ref "A4") (pin "4") (pinfunction "NC_4") (pintype "passive"))
      (node (ref "R38") (pin "1") (pinfunction "1_1") (pintype "passive"))
      (node (ref "R39") (pin "2") (pinfunction "2_2") (pintype "passive"))
    )
    (net (code "54") (name "Net-(A5-M1A)") (class "Default")
      (node (ref "A5") (pin "12") (pinfunction "M1A_12") (pintype "passive"))
      (node (ref "XP26") (pin "2") (pinfunction "2_2") (pintype "passive"))
    )
    (net (code "55") (name "Net-(A5-M1B)") (class "Default")
      (node (ref "A5") (pin "11") (pinfunction "M1B_11") (pintype "passive"))
      (node (ref "XP26") (pin "1") (pinfunction "1_1") (pintype "passive"))
    )
    (net (code "56") (name "Net-(A5-M2A)") (class "Default")
      (node (ref "A5") (pin "13") (pinfunction "M2A_13") (pintype "passive"))
      (node (ref "XP26") (pin "3") (pinfunction "3_3") (pintype "passive"))
    )
    (net (code "57") (name "Net-(A5-M2B)") (class "Default")
      (node (ref "A5") (pin "14") (pinfunction "M2B_14") (pintype "passive"))
      (node (ref "XP26") (pin "4") (pinfunction "4_4") (pintype "passive"))
    )
    (net (code "58") (name "Net-(A5-MS1)") (class "Default")
      (node (ref "A5") (pin "2") (pinfunction "MS1_2") (pintype "passive"))
      (node (ref "XP23") (pin "2") (pinfunction "2_2") (pintype "passive"))
    )
    (net (code "59") (name "Net-(A5-MS2)") (class "Default")
      (node (ref "A5") (pin "3") (pinfunction "MS2_3") (pintype "passive"))
      (node (ref "XP24") (pin "2") (pinfunction "2_2") (pintype "passive"))
    )
    (net (code "60") (name "Net-(A5-NC)") (class "Default")
      (node (ref "A5") (pin "4") (pinfunction "NC_4") (pintype "passive"))
      (node (ref "R42") (pin "1") (pinfunction "1_1") (pintype "passive"))
      (node (ref "R43") (pin "2") (pinfunction "2_2") (pintype "passive"))
    )
    (net (code "61") (name "Net-(R32-Pad1)") (class "Default")
      (node (ref "R32") (pin "1") (pinfunction "1_1") (pintype "passive"))
      (node (ref "XP11") (pin "2") (pinfunction "2_2") (pintype "passive"))
    )
    (net (code "62") (name "Net-(R33-Pad1)") (class "Default")
      (node (ref "R33") (pin "1") (pinfunction "1_1") (pintype "passive"))
      (node (ref "XP12") (pin "2") (pinfunction "2_2") (pintype "passive"))
    )
    (net (code "63") (name "Net-(R34-Pad2)") (class "Default")
      (node (ref "R34") (pin "2") (pinfunction "2_2") (pintype "passive"))
      (node (ref "VD5") (pin "Anode") (pinfunction "Anode_Anode") (pintype "passive"))
    )
    (net (code "64") (name "Net-(R35-Pad2)") (class "Default")
      (node (ref "R35") (pin "2") (pinfunction "2_2") (pintype "passive"))
      (node (ref "VD6") (pin "Anode") (pinfunction "Anode_Anode") (pintype "passive"))
    )
    (net (code "65") (name "Net-(R37-Pad1)") (class "Default")
      (node (ref "R37") (pin "1") (pinfunction "1_1") (pintype "passive"))
      (node (ref "XP19") (pin "2") (pinfunction "2_2") (pintype "passive"))
    )
    (net (code "66") (name "Net-(R39-Pad1)") (class "Default")
      (node (ref "R39") (pin "1") (pinfunction "1_1") (pintype "passive"))
      (node (ref "XP20") (pin "2") (pinfunction "2_2") (pintype "passive"))
    )
    (net (code "67") (name "Net-(R40-Pad2)") (class "Default")
      (node (ref "R40") (pin "2") (pinfunction "2_2") (pintype "passive"))
      (node (ref "VD7") (pin "Anode") (pinfunction "Anode_Anode") (pintype "passive"))
    )
    (net (code "68") (name "Net-(R41-Pad2)") (class "Default")
      (node (ref "R41") (pin "2") (pinfunction "2_2") (pintype "passive"))
      (node (ref "VD8") (pin "Anode") (pinfunction "Anode_Anode") (pintype "passive"))
    )
    (net (code "69") (name "Net-(R43-Pad1)") (class "Default")
      (node (ref "R43") (pin "1") (pinfunction "1_1") (pintype "passive"))
      (node (ref "XP25") (pin "2") (pinfunction "2_2") (pintype "passive"))
    )
    (net (code "70") (name "Net-(R45-Pad2)") (class "Default")
      (node (ref "R45") (pin "2") (pinfunction "2_2") (pintype "passive"))
      (node (ref "VD12") (pin "Anode") (pinfunction "Anode_Anode") (pintype "passive"))
    )
    (net (code "71") (name "unconnected-(A1-CLK-Pad6)") (class "Default")
      (node (ref "A1") (pin "6") (pinfunction "CLK_6") (pintype "passive"))
    )
    (net (code "72") (name "unconnected-(A1-VREF-Pad17)") (class "Default")
      (node (ref "A1") (pin "17") (pinfunction "VREF_17") (pintype "passive"))
    )
    (net (code "73") (name "unconnected-(A2-CLK-Pad6)") (class "Default")
      (node (ref "A2") (pin "6") (pinfunction "CLK_6") (pintype "passive"))
    )
    (net (code "74") (name "unconnected-(A2-VREF-Pad17)") (class "Default")
      (node (ref "A2") (pin "17") (pinfunction "VREF_17") (pintype "passive"))
    )
    (net (code "75") (name "unconnected-(A3-CLK-Pad6)") (class "Default")
      (node (ref "A3") (pin "6") (pinfunction "CLK_6") (pintype "passive"))
    )
    (net (code "76") (name "unconnected-(A3-VREF-Pad17)") (class "Default")
      (node (ref "A3") (pin "17") (pinfunction "VREF_17") (pintype "passive"))
    )
    (net (code "77") (name "unconnected-(A4-CLK-Pad6)") (class "Default")
      (node (ref "A4") (pin "6") (pinfunction "CLK_6") (pintype "passive"))
    )
    (net (code "78") (name "unconnected-(A4-VREF-Pad17)") (class "Default")
      (node (ref "A4") (pin "17") (pinfunction "VREF_17") (pintype "passive"))
    )
    (net (code "79") (name "unconnected-(A5-CLK-Pad6)") (class "Default")
      (node (ref "A5") (pin "6") (pinfunction "CLK_6") (pintype "passive"))
    )
    (net (code "80") (name "unconnected-(A5-VREF-Pad17)") (class "Default")
      (node (ref "A5") (pin "17") (pinfunction "VREF_17") (pintype "passive"))
    )
    (net (code "81") (name "unconnected-(VD11-Second_Diod_Anode-PadAnode2)") (class "Default")
      (node (ref "VD11") (pin "Anode2") (pinfunction "Second_Diod_Anode_Anode2") (pintype "passive"))
    )
  )
)
